# Experiment_1.net
KiCad netlist of a schematic drawn in Altium Designer
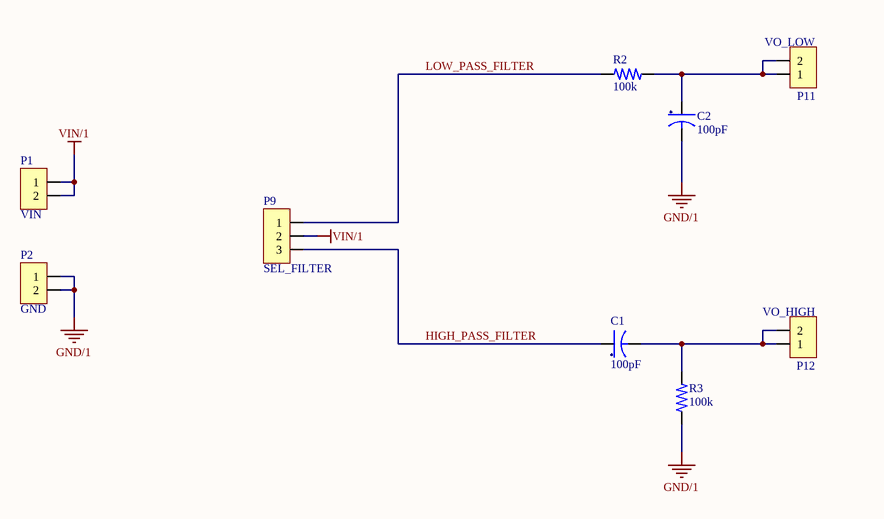
[diagram p0: Experiment 1.SchDoc]

(export (version "E")
  (design (tool "Eeschema 10.0.6"))
  (components
    (comp (ref "C1")
      (value "100pF")
      (footprint "C0805")
      (description "CAP CER 100PF 50V NPO 0805")
      (fields
        (field (name "MANUFACTURER") "Yageo")
        (field (name "MANUFACTURER PART NUMBER") "CC0805JRNPO9BN101")
      )
      (libsource (lib "Capacitors") (part "CC0805JRNPO9BN101"))
    )
    (comp (ref "C2")
      (value "100pF")
      (footprint "C0805")
      (description "CAP CER 100PF 50V NPO 0805")
      (fields
        (field (name "MANUFACTURER") "Yageo")
        (field (name "MANUFACTURER PART NUMBER") "CC0805JRNPO9BN101")
      )
      (libsource (lib "") (part "CC0805JRNPO9BN101_1"))
    )
    (comp (ref "P1")
      (value "VIN")
      (footprint "PINHD-1X02 ONCE")
      (description "CONN HEADER 2POS .100\" STR TIN")
      (fields
        (field (name "MANUFACTURER") "Molex, LLC")
        (field (name "MANUFACTURER PART NUMBER") "0901200122")
      )
      (libsource (lib "") (part "PIN HEADER 1X02 ONCE_1"))
    )
    (comp (ref "P2")
      (value "GND")
      (footprint "PINHD-1X02 ONCE")
      (description "CONN HEADER 2POS .100\" STR TIN")
      (fields
        (field (name "MANUFACTURER") "Molex, LLC")
        (field (name "MANUFACTURER PART NUMBER") "0901200122")
      )
      (libsource (lib "") (part "PIN HEADER 1X02 ONCE_1"))
    )
    (comp (ref "P9")
      (value "SEL_FILTER")
      (footprint "PINHD-1X03")
      (description "CONN HEADER 3POS .100\" STR TIN")
      (fields
        (field (name "MANUFACTURER") "Molex, LLC")
        (field (name "MANUFACTURER PART NUMBER") "0901200123")
      )
      (libsource (lib "Connectors") (part "PIN HEADER 1X03"))
    )
    (comp (ref "P11")
      (value "VO_LOW")
      (footprint "PINHD-1X02 ONCE")
      (description "CONN HEADER 2POS .100\" STR TIN")
      (fields
        (field (name "MANUFACTURER") "Molex, LLC")
        (field (name "MANUFACTURER PART NUMBER") "0901200122")
      )
      (libsource (lib "Connectors") (part "PIN HEADER 1X02 ONCE"))
    )
    (comp (ref "P12")
      (value "VO_HIGH")
      (footprint "PINHD-1X02 ONCE")
      (description "CONN HEADER 2POS .100\" STR TIN")
      (fields
        (field (name "MANUFACTURER") "Molex, LLC")
        (field (name "MANUFACTURER PART NUMBER") "0901200122")
      )
      (libsource (lib "Connectors") (part "PIN HEADER 1X02 ONCE"))
    )
    (comp (ref "R2")
      (value "100k")
      (footprint "R0805")
      (description "RES SMD 100K OHM 1% 1/8W 0805")
      (fields
        (field (name "MANUFACTURER") "Panasonic Electronic Components")
        (field (name "MANUFACTURER PART NUMBER") "ERJ-6ENF1003V")
      )
      (libsource (lib "Resistors") (part "ERJ-6ENF1003V"))
    )
    (comp (ref "R3")
      (value "100k")
      (footprint "R0805")
      (description "RES SMD 100K OHM 1% 1/8W 0805")
      (fields
        (field (name "MANUFACTURER") "Panasonic Electronic Components")
        (field (name "MANUFACTURER PART NUMBER") "ERJ-6ENF1003V")
      )
      (libsource (lib "Resistors") (part "ERJ-6ENF1003V"))
    )
  )
  (nets
    (net (code "1") (name "/HIGH_PASS_FILTER") (class "Default")
      (node (ref "C1") (pin "1") (pinfunction "1_1") (pintype "passive"))
      (node (ref "P9") (pin "3") (pinfunction "3_3") (pintype "passive"))
    )
    (net (code "2") (name "/LOW_PASS_FILTER") (class "Default")
      (node (ref "P9") (pin "1") (pinfunction "1_1") (pintype "passive"))
      (node (ref "R2") (pin "1") (pinfunction "1_1") (pintype "passive"))
    )
    (net (code "3") (name "GND{slash}1") (class "Default")
      (node (ref "C2") (pin "2") (pinfunction "2_2") (pintype "passive"))
      (node (ref "P2") (pin "1") (pinfunction "1_1") (pintype "passive"))
      (node (ref "P2") (pin "2") (pinfunction "2_2") (pintype "passive"))
      (node (ref "R3") (pin "1") (pinfunction "1_1") (pintype "passive"))
    )
    (net (code "4") (name "Net-(C1-Pad2)") (class "Default")
      (node (ref "C1") (pin "2") (pinfunction "2_2") (pintype "passive"))
      (node (ref "P12") (pin "1") (pinfunction "1_1") (pintype "passive"))
      (node (ref "P12") (pin "2") (pinfunction "2_2") (pintype "passive"))
      (node (ref "R3") (pin "2") (pinfunction "2_2") (pintype "passive"))
    )
    (net (code "5") (name "Net-(C2-Pad1)") (class "Default")
      (node (ref "C2") (pin "1") (pinfunction "1_1") (pintype "passive"))
      (node (ref "P11") (pin "1") (pinfunction "1_1") (pintype "passive"))
      (node (ref "P11") (pin "2") (pinfunction "2_2") (pintype "passive"))
      (node (ref "R2") (pin "2") (pinfunction "2_2") (pintype "passive"))
    )
    (net (code "6") (name "VIN{slash}1") (class "Default")
      (node (ref "P1") (pin "1") (pinfunction "1_1") (pintype "passive"))
      (node (ref "P1") (pin "2") (pinfunction "2_2") (pintype "passive"))
      (node (ref "P9") (pin "2") (pinfunction "2_2") (pintype "passive"))
    )
  )
)
